# A1-A1_Switches_Control_Logic.net
KiCad netlist of a schematic drawn in Altium Designer
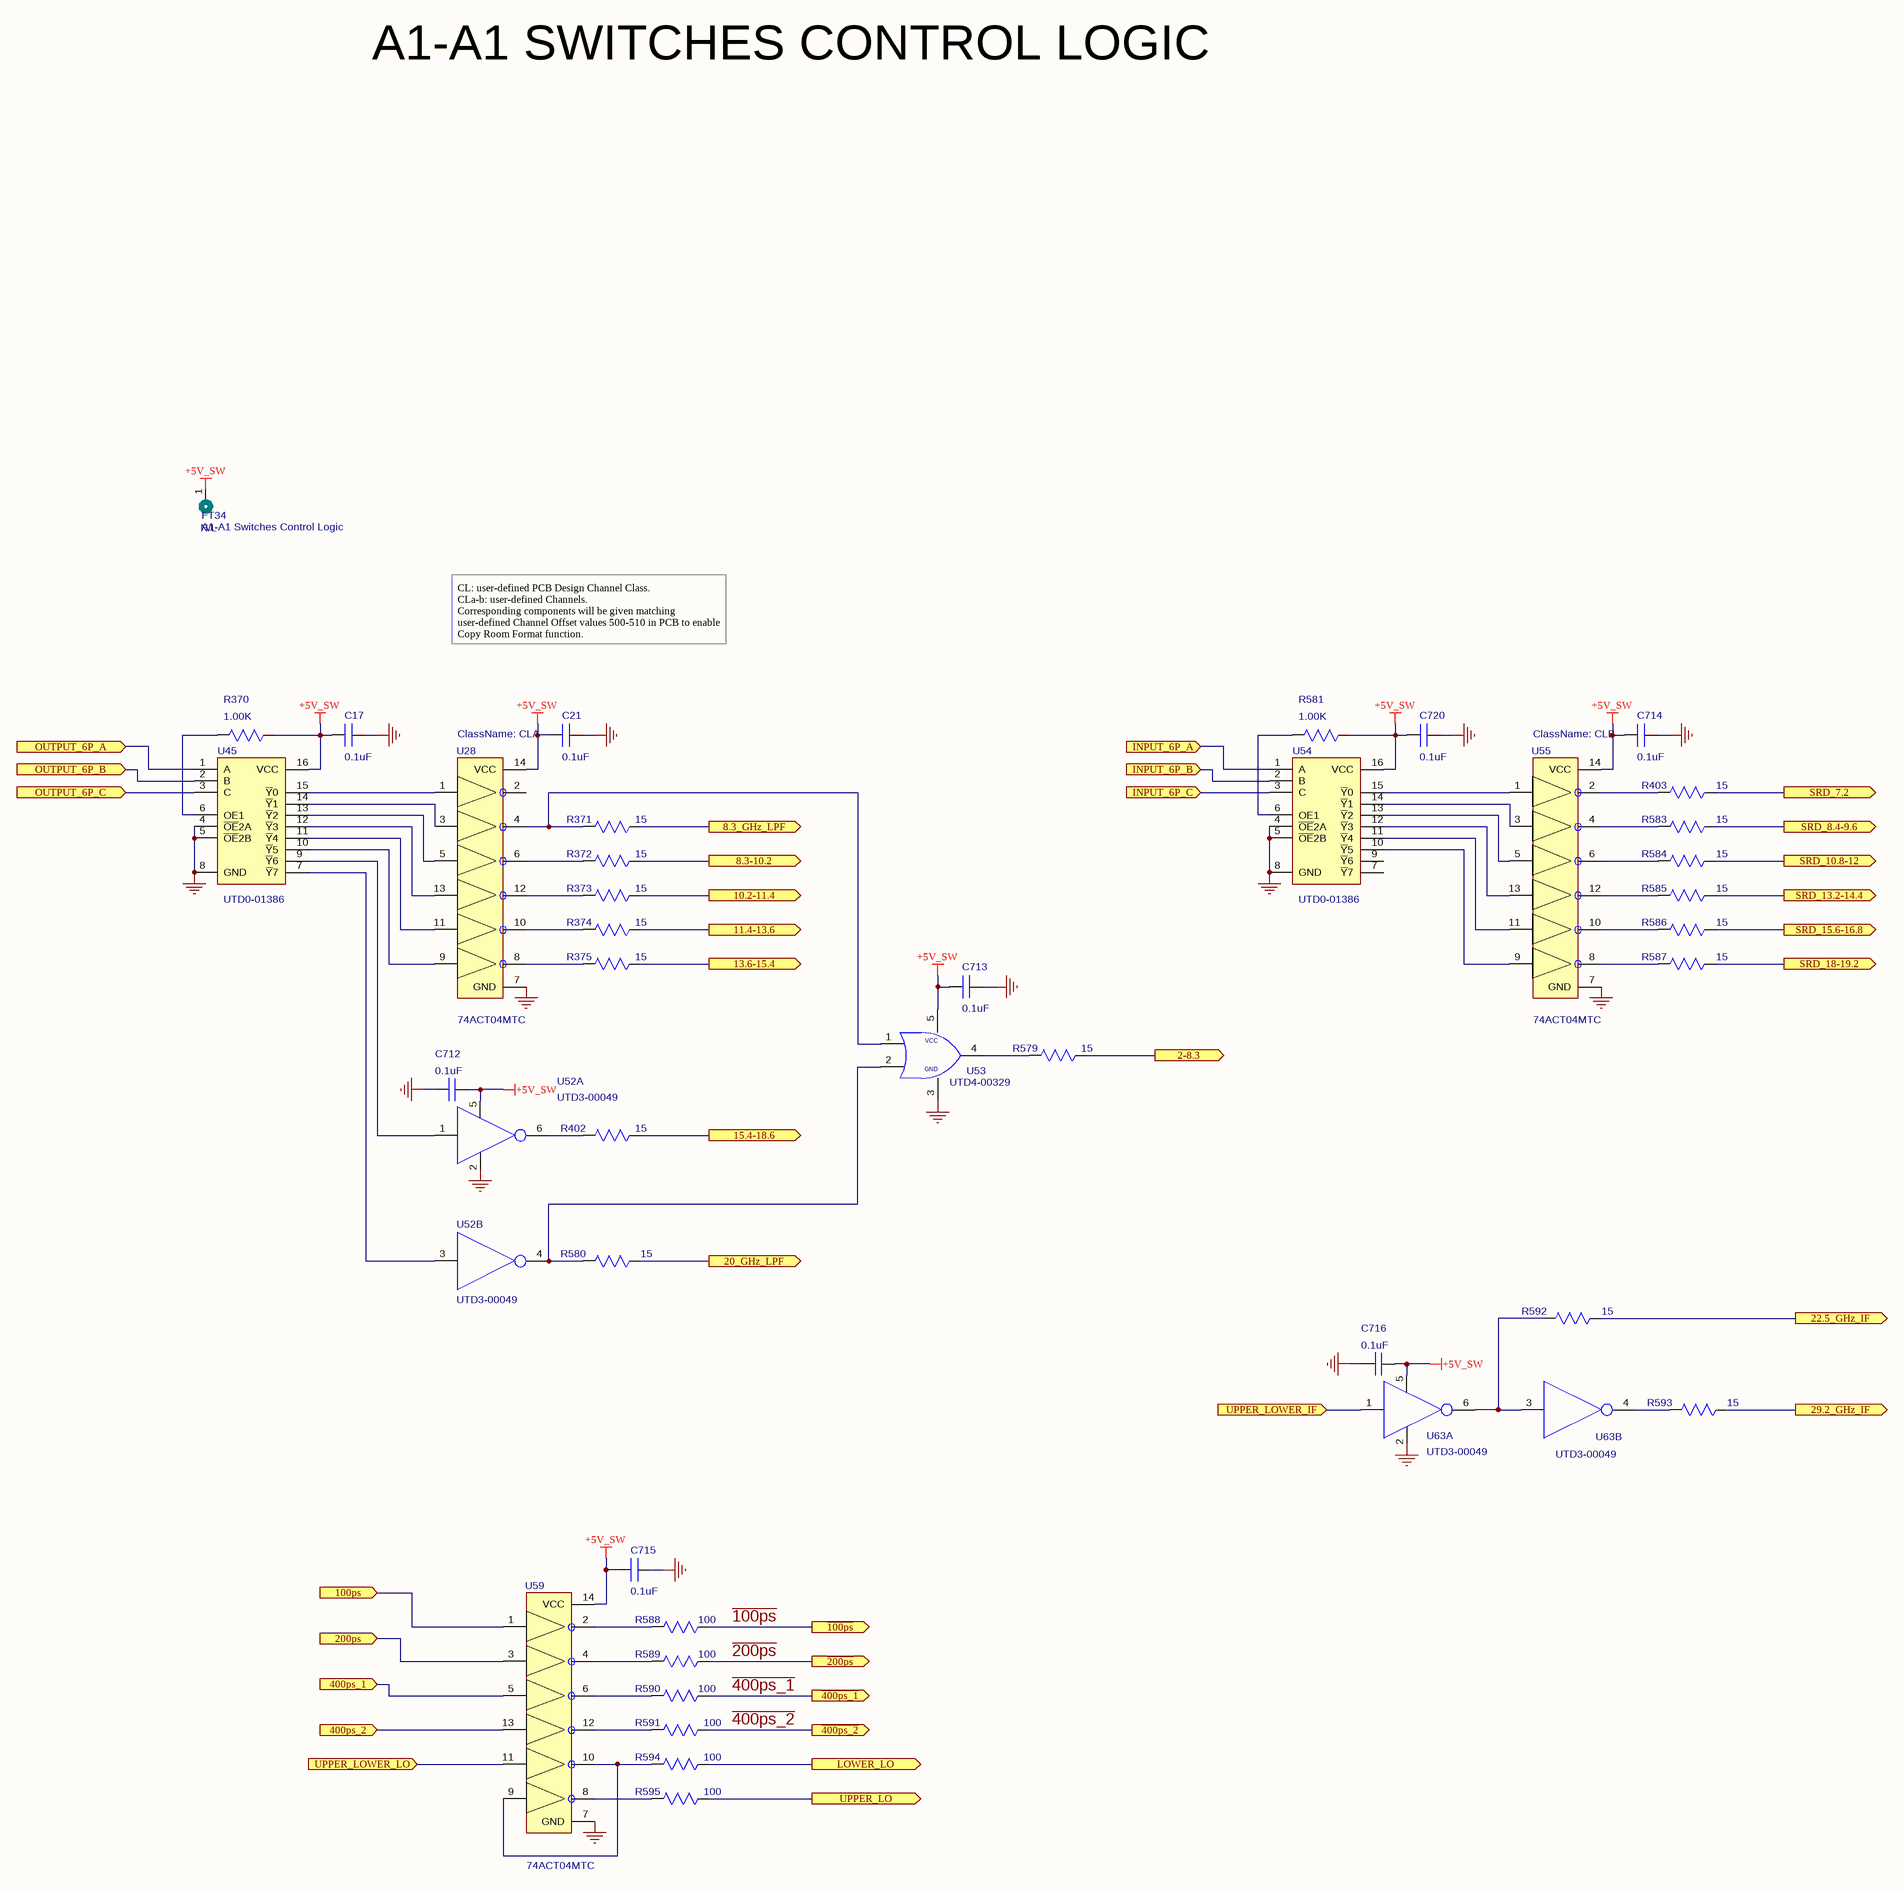
[diagram p0: A1-A1 Switches Control Logic.SchDoc]

(export (version "E")
  (design (tool "Eeschema 10.0.6"))
  (components
    (comp (ref "C17")
      (value "0.1uF")
      (footprint "CAP-0603-H035-N")
      (description ".1UF;10%;X7R;16V;CHIP;0603")
      (fields (field (name "APPROVED") "CL"))
      (libsource (lib "Giga-tronics") (part "CK45-04100"))
    )
    (comp (ref "C21")
      (value "0.1uF")
      (footprint "CAP-0603-H035-N")
      (description ".1UF;10%;X7R;16V;CHIP;0603")
      (fields (field (name "APPROVED") "CL"))
      (libsource (lib "Giga-tronics") (part "CK45-04100"))
    )
    (comp (ref "C712")
      (value "0.1uF")
      (footprint "CAP-0603-H035-N")
      (description ".1UF;10%;X7R;16V;CHIP;0603")
      (fields (field (name "APPROVED") "CL"))
      (libsource (lib "Giga-tronics") (part "CK45-04100"))
    )
    (comp (ref "C713")
      (value "0.1uF")
      (footprint "CAP-0603-H035-N")
      (description ".1UF;10%;X7R;16V;CHIP;0603")
      (fields (field (name "APPROVED") "CL"))
      (libsource (lib "Giga-tronics") (part "CK45-04100"))
    )
    (comp (ref "C714")
      (value "0.1uF")
      (footprint "CAP-0603-H035-N")
      (description ".1UF;10%;X7R;16V;CHIP;0603")
      (fields (field (name "APPROVED") "CL"))
      (libsource (lib "Giga-tronics") (part "CK45-04100"))
    )
    (comp (ref "C715")
      (value "0.1uF")
      (footprint "CAP-0603-H035-N")
      (description ".1UF;10%;X7R;16V;CHIP;0603")
      (fields (field (name "APPROVED") "CL"))
      (libsource (lib "Giga-tronics") (part "CK45-04100"))
    )
    (comp (ref "C716")
      (value "0.1uF")
      (footprint "CAP-0603-H035-N")
      (description ".1UF;10%;X7R;16V;CHIP;0603")
      (fields (field (name "APPROVED") "CL"))
      (libsource (lib "Giga-tronics") (part "CK45-04100"))
    )
    (comp (ref "C720")
      (value "0.1uF")
      (footprint "CAP-0603-H035-N")
      (description ".1UF;10%;X7R;16V;CHIP;0603")
      (fields (field (name "APPROVED") "CL"))
      (libsource (lib "Giga-tronics") (part "CK45-04100"))
    )
    (comp (ref "FT34")
      (value "A1-A1 Switches Control Logic")
      (footprint "FromToNode_ML2")
      (fields (field (name "NOLOAD") "N/L") (field (name "APPROVED") "*"))
      (libsource (lib "Giga-tronics") (part "FromToNode"))
    )
    (comp (ref "R370")
      (value "1.00K")
      (footprint "RES-0402-N")
      (description "1.0K OHMS;.06W;1%;200PPM;FILM;CHIP;0402")
      (fields (field (name "APPROVED") "CL"))
      (libsource (lib "Giga-tronics") (part "RK35-11000"))
    )
    (comp (ref "R371")
      (value "15")
      (footprint "RES-0402-N")
      (description "15 OHMS;.06W;1%;200PPM;FILM;CHIP;0402")
      (fields (field (name "APPROVED") "CL"))
      (libsource (lib "Giga-tronics") (part "RK35-00150"))
    )
    (comp (ref "R372")
      (value "15")
      (footprint "RES-0402-N")
      (description "15 OHMS;.06W;1%;200PPM;FILM;CHIP;0402")
      (fields (field (name "APPROVED") "CL"))
      (libsource (lib "Giga-tronics") (part "RK35-00150"))
    )
    (comp (ref "R373")
      (value "15")
      (footprint "RES-0402-N")
      (description "15 OHMS;.06W;1%;200PPM;FILM;CHIP;0402")
      (fields (field (name "APPROVED") "CL"))
      (libsource (lib "Giga-tronics") (part "RK35-00150"))
    )
    (comp (ref "R374")
      (value "15")
      (footprint "RES-0402-N")
      (description "15 OHMS;.06W;1%;200PPM;FILM;CHIP;0402")
      (fields (field (name "APPROVED") "CL"))
      (libsource (lib "Giga-tronics") (part "RK35-00150"))
    )
    (comp (ref "R375")
      (value "15")
      (footprint "RES-0402-N")
      (description "15 OHMS;.06W;1%;200PPM;FILM;CHIP;0402")
      (fields (field (name "APPROVED") "CL"))
      (libsource (lib "Giga-tronics") (part "RK35-00150"))
    )
    (comp (ref "R402")
      (value "15")
      (footprint "RES-0402-N")
      (description "15 OHMS;.06W;1%;200PPM;FILM;CHIP;0402")
      (fields (field (name "APPROVED") "CL"))
      (libsource (lib "Giga-tronics") (part "RK35-00150"))
    )
    (comp (ref "R403")
      (value "15")
      (footprint "RES-0402-N")
      (description "15 OHMS;.06W;1%;200PPM;FILM;CHIP;0402")
      (fields (field (name "APPROVED") "CL"))
      (libsource (lib "Giga-tronics") (part "RK35-00150"))
    )
    (comp (ref "R579")
      (value "15")
      (footprint "RES-0402-N")
      (description "15 OHMS;.06W;1%;200PPM;FILM;CHIP;0402")
      (fields (field (name "APPROVED") "CL"))
      (libsource (lib "Giga-tronics") (part "RK35-00150"))
    )
    (comp (ref "R580")
      (value "15")
      (footprint "RES-0402-N")
      (description "15 OHMS;.06W;1%;200PPM;FILM;CHIP;0402")
      (fields (field (name "APPROVED") "CL"))
      (libsource (lib "Giga-tronics") (part "RK35-00150"))
    )
    (comp (ref "R581")
      (value "1.00K")
      (footprint "RES-0402-N")
      (description "1.0K OHMS;.06W;1%;200PPM;FILM;CHIP;0402")
      (fields (field (name "APPROVED") "CL"))
      (libsource (lib "Giga-tronics") (part "RK35-11000"))
    )
    (comp (ref "R583")
      (value "15")
      (footprint "RES-0402-N")
      (description "15 OHMS;.06W;1%;200PPM;FILM;CHIP;0402")
      (fields (field (name "APPROVED") "CL"))
      (libsource (lib "Giga-tronics") (part "RK35-00150"))
    )
    (comp (ref "R584")
      (value "15")
      (footprint "RES-0402-N")
      (description "15 OHMS;.06W;1%;200PPM;FILM;CHIP;0402")
      (fields (field (name "APPROVED") "CL"))
      (libsource (lib "Giga-tronics") (part "RK35-00150"))
    )
    (comp (ref "R585")
      (value "15")
      (footprint "RES-0402-N")
      (description "15 OHMS;.06W;1%;200PPM;FILM;CHIP;0402")
      (fields (field (name "APPROVED") "CL"))
      (libsource (lib "Giga-tronics") (part "RK35-00150"))
    )
    (comp (ref "R586")
      (value "15")
      (footprint "RES-0402-N")
      (description "15 OHMS;.06W;1%;200PPM;FILM;CHIP;0402")
      (fields (field (name "APPROVED") "CL"))
      (libsource (lib "Giga-tronics") (part "RK35-00150"))
    )
    (comp (ref "R587")
      (value "15")
      (footprint "RES-0402-N")
      (description "15 OHMS;.06W;1%;200PPM;FILM;CHIP;0402")
      (fields (field (name "APPROVED") "CL"))
      (libsource (lib "Giga-tronics") (part "RK35-00150"))
    )
    (comp (ref "R588")
      (value "100")
      (footprint "RES-0402-N")
      (description "100 OHMS; 1%; .1W; 100PPM; FILM; CHIP; 0402")
      (fields (field (name "APPROVED") "CL"))
      (libsource (lib "Giga-tronics") (part "RK35-01000"))
    )
    (comp (ref "R589")
      (value "100")
      (footprint "RES-0402-N")
      (description "100 OHMS; 1%; .1W; 100PPM; FILM; CHIP; 0402")
      (fields (field (name "APPROVED") "CL"))
      (libsource (lib "Giga-tronics") (part "RK35-01000"))
    )
    (comp (ref "R590")
      (value "100")
      (footprint "RES-0402-N")
      (description "100 OHMS; 1%; .1W; 100PPM; FILM; CHIP; 0402")
      (fields (field (name "APPROVED") "CL"))
      (libsource (lib "Giga-tronics") (part "RK35-01000"))
    )
    (comp (ref "R591")
      (value "100")
      (footprint "RES-0402-N")
      (description "100 OHMS; 1%; .1W; 100PPM; FILM; CHIP; 0402")
      (fields (field (name "APPROVED") "CL"))
      (libsource (lib "Giga-tronics") (part "RK35-01000"))
    )
    (comp (ref "R592")
      (value "15")
      (footprint "RES-0402-N")
      (description "15 OHMS;.06W;1%;200PPM;FILM;CHIP;0402")
      (fields (field (name "APPROVED") "CL"))
      (libsource (lib "Giga-tronics") (part "RK35-00150"))
    )
    (comp (ref "R593")
      (value "15")
      (footprint "RES-0402-N")
      (description "15 OHMS;.06W;1%;200PPM;FILM;CHIP;0402")
      (fields (field (name "APPROVED") "CL"))
      (libsource (lib "Giga-tronics") (part "RK35-00150"))
    )
    (comp (ref "R594")
      (value "100")
      (footprint "RES-0402-N")
      (description "100 OHMS; 1%; .1W; 100PPM; FILM; CHIP; 0402")
      (fields (field (name "APPROVED") "CL"))
      (libsource (lib "Giga-tronics") (part "RK35-01000"))
    )
    (comp (ref "R595")
      (value "100")
      (footprint "RES-0402-N")
      (description "100 OHMS; 1%; .1W; 100PPM; FILM; CHIP; 0402")
      (fields (field (name "APPROVED") "CL"))
      (libsource (lib "Giga-tronics") (part "RK35-01000"))
    )
    (comp (ref "U28")
      (value "74ACT04MTC HEX INVERTER;SMT;TSSOP-14")
      (footprint "TSOP65P640X120-14L")
      (fields
        (field (name "M_PN") "74ACT04MTC")
        (field (name "CLASSNAME") "CLA")
        (field (name "APPROVED") "NM")
      )
      (libsource (lib "Giga-tronics") (part "UTD4-00046"))
    )
    (comp (ref "U45")
      (value "UTD0-01386")
      (footprint "SOIC16_MS-012")
      (description "3 TO 8 DECODER/DEMULTIPLEXER;74ACT138 LOGIC;SO-16")
      (fields (field (name "G_PN") "UTD0-01386") (field (name "APPROVED") "NM"))
      (libsource (lib "Giga-tronics") (part "UTD0-01386"))
    )
    (comp (ref "U52")
      (value "INVERTER;DUAL;1.65-5.5V SUP;2NS TPD;SC70-6")
      (footprint "SOT-363_419B")
      (fields (field (name "G_PN") "UTD3-00049") (field (name "APPROVED") "CL"))
      (libsource (lib "Giga-tronics") (part "UTD3-00049"))
    )
    (comp (ref "U53")
      (value "M74VHC1GT32DFT1G SGL OR SOT-353 RoHS")
      (footprint "SOT-353_ONSEMI")
      (fields (field (name "G_PN") "UTD4-00329") (field (name "APPROVED") "CL"))
      (libsource (lib "Giga-tronics") (part "UTD4-00329"))
    )
    (comp (ref "U54")
      (value "UTD0-01386")
      (footprint "SOIC16_MS-012")
      (description "3 TO 8 DECODER/DEMULTIPLEXER;74ACT138 LOGIC;SO-16")
      (fields (field (name "G_PN") "UTD0-01386") (field (name "APPROVED") "NM"))
      (libsource (lib "Giga-tronics") (part "UTD0-01386"))
    )
    (comp (ref "U55")
      (value "74ACT04MTC HEX INVERTER;SMT;TSSOP-14")
      (footprint "TSOP65P640X120-14L")
      (fields
        (field (name "M_PN") "74ACT04MTC")
        (field (name "CLASSNAME") "CLB")
        (field (name "APPROVED") "NM")
      )
      (libsource (lib "Giga-tronics") (part "UTD4-00046"))
    )
    (comp (ref "U59")
      (value "74ACT04MTC HEX INVERTER;SMT;TSSOP-14")
      (footprint "TSOP65P640X120-14L")
      (fields (field (name "M_PN") "74ACT04MTC") (field (name "APPROVED") "NM"))
      (libsource (lib "Giga-tronics") (part "UTD4-00046"))
    )
    (comp (ref "U63")
      (value "INVERTER;DUAL;1.65-5.5V SUP;2NS TPD;SC70-6")
      (footprint "SOT-363_419B")
      (fields (field (name "G_PN") "UTD3-00049") (field (name "APPROVED") "CL"))
      (libsource (lib "Giga-tronics") (part "UTD3-00049"))
    )
  )
  (nets
    (net (code "1") (name "+5V_SW") (class "Default")
      (node (ref "C17") (pin "1") (pintype "passive"))
      (node (ref "C21") (pin "1") (pintype "passive"))
      (node (ref "C712") (pin "1") (pintype "passive"))
      (node (ref "C713") (pin "1") (pintype "passive"))
      (node (ref "C714") (pin "1") (pintype "passive"))
      (node (ref "C715") (pin "1") (pintype "passive"))
      (node (ref "C716") (pin "1") (pintype "passive"))
      (node (ref "C720") (pin "1") (pintype "passive"))
      (node (ref "FT34") (pin "1") (pinfunction "1_1") (pintype "passive"))
      (node (ref "R370") (pin "2") (pintype "passive"))
      (node (ref "R581") (pin "2") (pintype "passive"))
      (node (ref "U28") (pin "14") (pinfunction "VCC_14") (pintype "passive"))
      (node (ref "U45") (pin "16") (pinfunction "VCC_16") (pintype "passive"))
      (node (ref "U52") (pin "5") (pinfunction "V+_5") (pintype "passive"))
      (node (ref "U53") (pin "5") (pinfunction "VCC_5") (pintype "passive"))
      (node (ref "U54") (pin "16") (pinfunction "VCC_16") (pintype "passive"))
      (node (ref "U55") (pin "14") (pinfunction "VCC_14") (pintype "passive"))
      (node (ref "U59") (pin "14") (pinfunction "VCC_14") (pintype "passive"))
      (node (ref "U63") (pin "5") (pinfunction "V+_5") (pintype "passive"))
    )
    (net (code "2") (name "/2-8.3") (class "Default") (node (ref "R579") (pin "2") (pintype "passive")))
    (net (code "3") (name "/8.3-10.2") (class "Default") (node (ref "R372") (pin "2") (pintype "passive")))
    (net (code "4") (name "/8.3_GHz_LPF") (class "Default") (node (ref "R371") (pin "2") (pintype "passive")))
    (net (code "5") (name "/10.2-11.4") (class "Default") (node (ref "R373") (pin "2") (pintype "passive")))
    (net (code "6") (name "/11.4-13.6") (class "Default") (node (ref "R374") (pin "2") (pintype "passive")))
    (net (code "7") (name "/13.6-15.4") (class "Default") (node (ref "R375") (pin "2") (pintype "passive")))
    (net (code "8") (name "/15.4-18.6") (class "Default") (node (ref "R402") (pin "2") (pintype "passive")))
    (net (code "9") (name "/20_GHz_LPF") (class "Default") (node (ref "R580") (pin "2") (pintype "passive")))
    (net (code "10") (name "/22.5_GHz_IF") (class "Default")
      (node (ref "R592") (pin "2") (pintype "passive"))
    )
    (net (code "11") (name "/29.2_GHz_IF") (class "Default")
      (node (ref "R593") (pin "2") (pintype "passive"))
    )
    (net (code "12") (name "/100ps") (class "Default") (node (ref "U59") (pin "1") (pintype "passive")))
    (net (code "13") (name "/200ps") (class "Default") (node (ref "U59") (pin "3") (pintype "passive")))
    (net (code "14") (name "/400ps_1") (class "Default") (node (ref "U59") (pin "5") (pintype "passive")))
    (net (code "15") (name "/400ps_2") (class "Default") (node (ref "U59") (pin "13") (pintype "passive")))
    (net (code "16") (name "/INPUT_6P_A") (class "Default")
      (node (ref "U54") (pin "1") (pinfunction "A_1") (pintype "passive"))
    )
    (net (code "17") (name "/INPUT_6P_B") (class "Default")
      (node (ref "U54") (pin "2") (pinfunction "B_2") (pintype "passive"))
    )
    (net (code "18") (name "/INPUT_6P_C") (class "Default")
      (node (ref "U54") (pin "3") (pinfunction "C_3") (pintype "passive"))
    )
    (net (code "19") (name "/LOWER_LO") (class "Default") (node (ref "R594") (pin "2") (pintype "passive")))
    (net (code "20") (name "/OUTPUT_6P_A") (class "Default")
      (node (ref "U45") (pin "1") (pinfunction "A_1") (pintype "passive"))
    )
    (net (code "21") (name "/OUTPUT_6P_B") (class "Default")
      (node (ref "U45") (pin "2") (pinfunction "B_2") (pintype "passive"))
    )
    (net (code "22") (name "/OUTPUT_6P_C") (class "Default")
      (node (ref "U45") (pin "3") (pinfunction "C_3") (pintype "passive"))
    )
    (net (code "23") (name "/SRD_7.2") (class "Default") (node (ref "R403") (pin "2") (pintype "passive")))
    (net (code "24") (name "/SRD_8.4-9.6") (class "Default")
      (node (ref "R583") (pin "2") (pintype "passive"))
    )
    (net (code "25") (name "/SRD_10.8-12") (class "Default")
      (node (ref "R584") (pin "2") (pintype "passive"))
    )
    (net (code "26") (name "/SRD_13.2-14.4") (class "Default")
      (node (ref "R585") (pin "2") (pintype "passive"))
    )
    (net (code "27") (name "/SRD_15.6-16.8") (class "Default")
      (node (ref "R586") (pin "2") (pintype "passive"))
    )
    (net (code "28") (name "/SRD_18-19.2") (class "Default")
      (node (ref "R587") (pin "2") (pintype "passive"))
    )
    (net (code "29") (name "/UPPER_LO") (class "Default") (node (ref "R595") (pin "2") (pintype "passive")))
    (net (code "30") (name "/UPPER_LOWER_IF") (class "Default")
      (node (ref "U63") (pin "1") (pinfunction "IN_1") (pintype "passive"))
    )
    (net (code "31") (name "/UPPER_LOWER_LO") (class "Default")
      (node (ref "U59") (pin "11") (pintype "passive"))
    )
    (net (code "32") (name "/~{100ps}") (class "Default") (node (ref "R588") (pin "2") (pintype "passive")))
    (net (code "33") (name "/~{200ps}") (class "Default") (node (ref "R589") (pin "2") (pintype "passive")))
    (net (code "34") (name "/~{400ps_1}") (class "Default") (node (ref "R590") (pin "2") (pintype "passive")))
    (net (code "35") (name "/~{400ps_2}") (class "Default") (node (ref "R591") (pin "2") (pintype "passive")))
    (net (code "36") (name "GND") (class "Default")
      (node (ref "C17") (pin "2") (pintype "passive"))
      (node (ref "C21") (pin "2") (pintype "passive"))
      (node (ref "C712") (pin "2") (pintype "passive"))
      (node (ref "C713") (pin "2") (pintype "passive"))
      (node (ref "C714") (pin "2") (pintype "passive"))
      (node (ref "C715") (pin "2") (pintype "passive"))
      (node (ref "C716") (pin "2") (pintype "passive"))
      (node (ref "C720") (pin "2") (pintype "passive"))
      (node (ref "U28") (pin "7") (pinfunction "GND_7") (pintype "passive"))
      (node (ref "U45") (pin "4") (pinfunction "~{OE}2A_4") (pintype "passive"))
      (node (ref "U45") (pin "5") (pinfunction "~{OE}2B_5") (pintype "passive"))
      (node (ref "U45") (pin "8") (pinfunction "GND_8") (pintype "passive"))
      (node (ref "U52") (pin "2") (pinfunction "V-_2") (pintype "passive"))
      (node (ref "U53") (pin "3") (pinfunction "GND_3") (pintype "passive"))
      (node (ref "U54") (pin "4") (pinfunction "~{OE}2A_4") (pintype "passive"))
      (node (ref "U54") (pin "5") (pinfunction "~{OE}2B_5") (pintype "passive"))
      (node (ref "U54") (pin "8") (pinfunction "GND_8") (pintype "passive"))
      (node (ref "U55") (pin "7") (pinfunction "GND_7") (pintype "passive"))
      (node (ref "U59") (pin "7") (pinfunction "GND_7") (pintype "passive"))
      (node (ref "U63") (pin "2") (pinfunction "V-_2") (pintype "passive"))
    )
    (net (code "37") (name "Net-(R372-Pad1)") (class "Default")
      (node (ref "R372") (pin "1") (pintype "passive"))
      (node (ref "U28") (pin "6") (pintype "passive"))
    )
    (net (code "38") (name "Net-(R373-Pad1)") (class "Default")
      (node (ref "R373") (pin "1") (pintype "passive"))
      (node (ref "U28") (pin "12") (pintype "passive"))
    )
    (net (code "39") (name "Net-(R374-Pad1)") (class "Default")
      (node (ref "R374") (pin "1") (pintype "passive"))
      (node (ref "U28") (pin "10") (pintype "passive"))
    )
    (net (code "40") (name "Net-(R375-Pad1)") (class "Default")
      (node (ref "R375") (pin "1") (pintype "passive"))
      (node (ref "U28") (pin "8") (pintype "passive"))
    )
    (net (code "41") (name "Net-(R403-Pad1)") (class "Default")
      (node (ref "R403") (pin "1") (pintype "passive"))
      (node (ref "U55") (pin "2") (pintype "passive"))
    )
    (net (code "42") (name "Net-(R583-Pad1)") (class "Default")
      (node (ref "R583") (pin "1") (pintype "passive"))
      (node (ref "U55") (pin "4") (pintype "passive"))
    )
    (net (code "43") (name "Net-(R584-Pad1)") (class "Default")
      (node (ref "R584") (pin "1") (pintype "passive"))
      (node (ref "U55") (pin "6") (pintype "passive"))
    )
    (net (code "44") (name "Net-(R585-Pad1)") (class "Default")
      (node (ref "R585") (pin "1") (pintype "passive"))
      (node (ref "U55") (pin "12") (pintype "passive"))
    )
    (net (code "45") (name "Net-(R586-Pad1)") (class "Default")
      (node (ref "R586") (pin "1") (pintype "passive"))
      (node (ref "U55") (pin "10") (pintype "passive"))
    )
    (net (code "46") (name "Net-(R587-Pad1)") (class "Default")
      (node (ref "R587") (pin "1") (pintype "passive"))
      (node (ref "U55") (pin "8") (pintype "passive"))
    )
    (net (code "47") (name "Net-(R588-Pad1)") (class "Default")
      (node (ref "R588") (pin "1") (pintype "passive"))
      (node (ref "U59") (pin "2") (pintype "passive"))
    )
    (net (code "48") (name "Net-(R589-Pad1)") (class "Default")
      (node (ref "R589") (pin "1") (pintype "passive"))
      (node (ref "U59") (pin "4") (pintype "passive"))
    )
    (net (code "49") (name "Net-(R590-Pad1)") (class "Default")
      (node (ref "R590") (pin "1") (pintype "passive"))
      (node (ref "U59") (pin "6") (pintype "passive"))
    )
    (net (code "50") (name "Net-(R591-Pad1)") (class "Default")
      (node (ref "R591") (pin "1") (pintype "passive"))
      (node (ref "U59") (pin "12") (pintype "passive"))
    )
    (net (code "51") (name "Net-(R594-Pad1)") (class "Default")
      (node (ref "R594") (pin "1") (pintype "passive"))
      (node (ref "U59") (pin "10") (pintype "passive"))
      (node (ref "U59") (pin "9") (pintype "passive"))
    )
    (net (code "52") (name "Net-(R595-Pad1)") (class "Default")
      (node (ref "R595") (pin "1") (pintype "passive"))
      (node (ref "U59") (pin "8") (pintype "passive"))
    )
    (net (code "53") (name "Net-(U45-OE1)") (class "Default")
      (node (ref "R370") (pin "1") (pintype "passive"))
      (node (ref "U45") (pin "6") (pinfunction "OE1_6") (pintype "passive"))
    )
    (net (code "54") (name "Net-(U45-~{Y}0)") (class "Default")
      (node (ref "U28") (pin "1") (pintype "passive"))
      (node (ref "U45") (pin "15") (pinfunction "~{Y}0_15") (pintype "passive"))
    )
    (net (code "55") (name "Net-(U45-~{Y}1)") (class "Default")
      (node (ref "U28") (pin "3") (pintype "passive"))
      (node (ref "U45") (pin "14") (pinfunction "~{Y}1_14") (pintype "passive"))
    )
    (net (code "56") (name "Net-(U45-~{Y}2)") (class "Default")
      (node (ref "U28") (pin "5") (pintype "passive"))
      (node (ref "U45") (pin "13") (pinfunction "~{Y}2_13") (pintype "passive"))
    )
    (net (code "57") (name "Net-(U45-~{Y}3)") (class "Default")
      (node (ref "U28") (pin "13") (pintype "passive"))
      (node (ref "U45") (pin "12") (pinfunction "~{Y}3_12") (pintype "passive"))
    )
    (net (code "58") (name "Net-(U45-~{Y}4)") (class "Default")
      (node (ref "U28") (pin "11") (pintype "passive"))
      (node (ref "U45") (pin "11") (pinfunction "~{Y}4_11") (pintype "passive"))
    )
    (net (code "59") (name "Net-(U45-~{Y}5)") (class "Default")
      (node (ref "U28") (pin "9") (pintype "passive"))
      (node (ref "U45") (pin "10") (pinfunction "~{Y}5_10") (pintype "passive"))
    )
    (net (code "60") (name "Net-(U45-~{Y}6)") (class "Default")
      (node (ref "U45") (pin "9") (pinfunction "~{Y}6_9") (pintype "passive"))
      (node (ref "U52") (pin "1") (pinfunction "IN_1") (pintype "passive"))
    )
    (net (code "61") (name "Net-(U45-~{Y}7)") (class "Default")
      (node (ref "U45") (pin "7") (pinfunction "~{Y}7_7") (pintype "passive"))
      (node (ref "U52") (pin "3") (pinfunction "IN_3") (pintype "passive"))
    )
    (net (code "62") (name "Net-(U52A-OUT)") (class "Default")
      (node (ref "R402") (pin "1") (pintype "passive"))
      (node (ref "U52") (pin "6") (pinfunction "OUT_6") (pintype "passive"))
    )
    (net (code "63") (name "Net-(U52B-OUT)") (class "Default")
      (node (ref "R580") (pin "1") (pintype "passive"))
      (node (ref "U52") (pin "4") (pinfunction "OUT_4") (pintype "passive"))
      (node (ref "U53") (pin "2") (pinfunction "A_2") (pintype "passive"))
    )
    (net (code "64") (name "Net-(U53-B)") (class "Default")
      (node (ref "R371") (pin "1") (pintype "passive"))
      (node (ref "U28") (pin "4") (pintype "passive"))
      (node (ref "U53") (pin "1") (pinfunction "B_1") (pintype "passive"))
    )
    (net (code "65") (name "Net-(U53-Y)") (class "Default")
      (node (ref "R579") (pin "1") (pintype "passive"))
      (node (ref "U53") (pin "4") (pinfunction "Y_4") (pintype "passive"))
    )
    (net (code "66") (name "Net-(U54-OE1)") (class "Default")
      (node (ref "R581") (pin "1") (pintype "passive"))
      (node (ref "U54") (pin "6") (pinfunction "OE1_6") (pintype "passive"))
    )
    (net (code "67") (name "Net-(U54-~{Y}0)") (class "Default")
      (node (ref "U54") (pin "15") (pinfunction "~{Y}0_15") (pintype "passive"))
      (node (ref "U55") (pin "1") (pintype "passive"))
    )
    (net (code "68") (name "Net-(U54-~{Y}1)") (class "Default")
      (node (ref "U54") (pin "14") (pinfunction "~{Y}1_14") (pintype "passive"))
      (node (ref "U55") (pin "3") (pintype "passive"))
    )
    (net (code "69") (name "Net-(U54-~{Y}2)") (class "Default")
      (node (ref "U54") (pin "13") (pinfunction "~{Y}2_13") (pintype "passive"))
      (node (ref "U55") (pin "5") (pintype "passive"))
    )
    (net (code "70") (name "Net-(U54-~{Y}3)") (class "Default")
      (node (ref "U54") (pin "12") (pinfunction "~{Y}3_12") (pintype "passive"))
      (node (ref "U55") (pin "13") (pintype "passive"))
    )
    (net (code "71") (name "Net-(U54-~{Y}4)") (class "Default")
      (node (ref "U54") (pin "11") (pinfunction "~{Y}4_11") (pintype "passive"))
      (node (ref "U55") (pin "11") (pintype "passive"))
    )
    (net (code "72") (name "Net-(U54-~{Y}5)") (class "Default")
      (node (ref "U54") (pin "10") (pinfunction "~{Y}5_10") (pintype "passive"))
      (node (ref "U55") (pin "9") (pintype "passive"))
    )
    (net (code "73") (name "Net-(U63A-OUT)") (class "Default")
      (node (ref "R592") (pin "1") (pintype "passive"))
      (node (ref "U63") (pin "3") (pinfunction "IN_3") (pintype "passive"))
      (node (ref "U63") (pin "6") (pinfunction "OUT_6") (pintype "passive"))
    )
    (net (code "74") (name "Net-(U63B-OUT)") (class "Default")
      (node (ref "R593") (pin "1") (pintype "passive"))
      (node (ref "U63") (pin "4") (pinfunction "OUT_4") (pintype "passive"))
    )
    (net (code "75") (name "unconnected-(U28-Pad2)") (class "Default")
      (node (ref "U28") (pin "2") (pintype "passive"))
    )
    (net (code "76") (name "unconnected-(U54-~{Y}6-Pad9)") (class "Default")
      (node (ref "U54") (pin "9") (pinfunction "~{Y}6_9") (pintype "passive"))
    )
    (net (code "77") (name "unconnected-(U54-~{Y}7-Pad7)") (class "Default")
      (node (ref "U54") (pin "7") (pinfunction "~{Y}7_7") (pintype "passive"))
    )
  )
)
